# PCB__ARDUINO_APDS9960.net
KiCad netlist of a schematic drawn in EAGLE
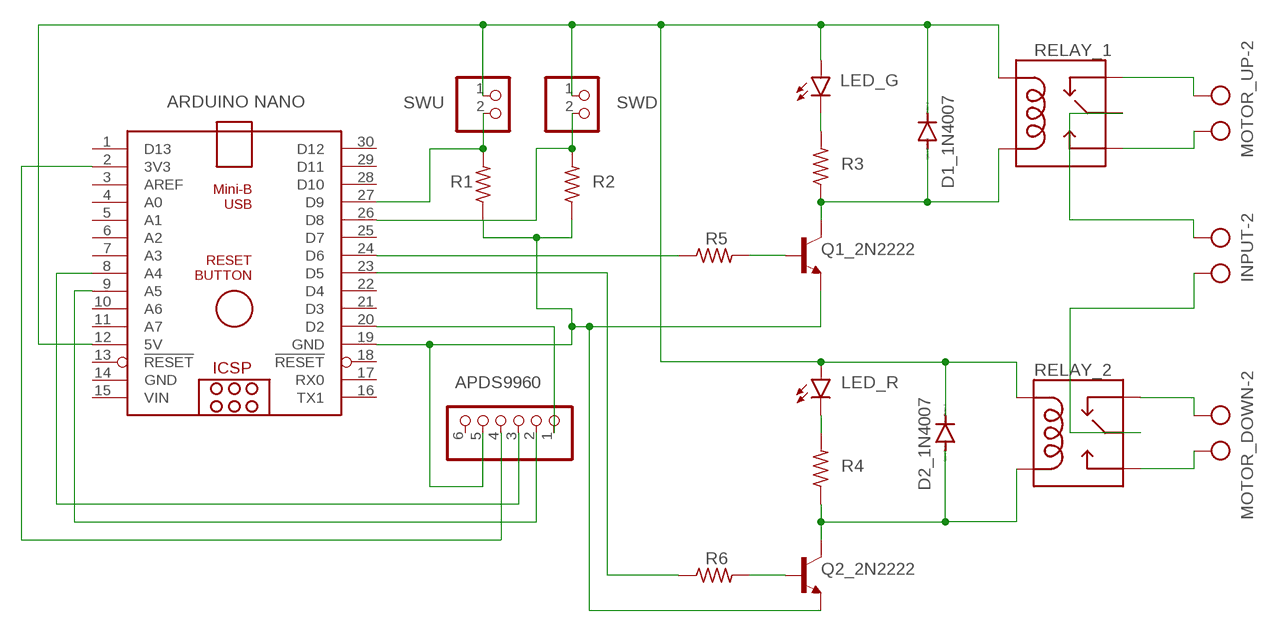
[diagram p0: schematic, sheet 1]

(export (version "E")
  (design (tool "Eeschema 10.0.6"))
  (components
    (comp (ref "APDS9960")
      (value "PINHD-1X6")
      (footprint "eagle-import:1X06")
      (libsource (lib "eagle-import") (part "PINHD-1X6"))
    )
    (comp (ref "ARDUINO_NANO")
      (value "ARDUINO NANO")
      (footprint "eagle-import:ARDUINO_NANO")
      (libsource (lib "eagle-import") (part "ARDUINO_NANO"))
    )
    (comp (ref "D1_1N4007")
      (value "1N4446")
      (footprint "eagle-import:DO35-10")
      (libsource (lib "eagle-import") (part "1N4446"))
    )
    (comp (ref "D2_1N4007")
      (value "1N4446")
      (footprint "eagle-import:DO35-10")
      (libsource (lib "eagle-import") (part "1N4446"))
    )
    (comp (ref "INPUT")
      (value "AK500/2")
      (footprint "eagle-import:AK500_2")
      (libsource (lib "eagle-import") (part "AK500/2"))
    )
    (comp (ref "LED_G")
      (value "TLLY4400")
      (footprint "eagle-import:LED3MM")
      (fields (field (name "MF") "VISHAY SEMICONDUCTOR"))
      (libsource (lib "eagle-import") (part "TLLY4400"))
    )
    (comp (ref "LED_R")
      (value "TLLY4400")
      (footprint "eagle-import:LED3MM")
      (fields (field (name "MF") "VISHAY SEMICONDUCTOR"))
      (libsource (lib "eagle-import") (part "TLLY4400"))
    )
    (comp (ref "MOTOR_DOWN")
      (value "AK500/2")
      (footprint "eagle-import:AK500_2")
      (libsource (lib "eagle-import") (part "AK500/2"))
    )
    (comp (ref "MOTOR_UP")
      (value "AK500/2")
      (footprint "eagle-import:AK500_2")
      (libsource (lib "eagle-import") (part "AK500/2"))
    )
    (comp (ref "Q1_2N2222")
      (value "2N3904")
      (footprint "eagle-import:TO92")
      (libsource (lib "eagle-import") (part "2N3904"))
    )
    (comp (ref "Q2_2N2222")
      (value "2N3904")
      (footprint "eagle-import:TO92")
      (libsource (lib "eagle-import") (part "2N3904"))
    )
    (comp (ref "R1")
      (value "R-US_0207/10")
      (footprint "eagle-import:0207_10")
      (libsource (lib "eagle-import") (part "R-US_0207/10"))
    )
    (comp (ref "R2")
      (value "R-US_0207/10")
      (footprint "eagle-import:0207_10")
      (libsource (lib "eagle-import") (part "R-US_0207/10"))
    )
    (comp (ref "R3")
      (value "R-US_0207/10")
      (footprint "eagle-import:0207_10")
      (libsource (lib "eagle-import") (part "R-US_0207/10"))
    )
    (comp (ref "R4")
      (value "R-US_0207/10")
      (footprint "eagle-import:0207_10")
      (libsource (lib "eagle-import") (part "R-US_0207/10"))
    )
    (comp (ref "R5")
      (value "R-US_0207/10")
      (footprint "eagle-import:0207_10")
      (libsource (lib "eagle-import") (part "R-US_0207/10"))
    )
    (comp (ref "R6")
      (value "R-US_0207/10")
      (footprint "eagle-import:0207_10")
      (libsource (lib "eagle-import") (part "R-US_0207/10"))
    )
    (comp (ref "RELAY_1")
      (value "RELAYPTH")
      (footprint "eagle-import:SRD-05VDC-SL-C")
      (libsource (lib "eagle-import") (part "RELAYPTH"))
    )
    (comp (ref "RELAY_2")
      (value "RELAYPTH")
      (footprint "eagle-import:SRD-05VDC-SL-C")
      (libsource (lib "eagle-import") (part "RELAYPTH"))
    )
    (comp (ref "SWD")
      (value "PINHD-1X2")
      (footprint "eagle-import:1X02")
      (libsource (lib "eagle-import") (part "PINHD-1X2"))
    )
    (comp (ref "SWU")
      (value "PINHD-1X2")
      (footprint "eagle-import:1X02")
      (libsource (lib "eagle-import") (part "PINHD-1X2"))
    )
  )
  (nets
    (net (code "1") (name "/GND") (class "Default")
      (node (ref "ARDUINO_NANO") (pin "14") (pinfunction "GND_14") (pintype "power_in"))
    )
    (net (code "2") (name "/VIN") (class "Default")
      (node (ref "ARDUINO_NANO") (pin "15") (pinfunction "VIN_15") (pintype "power_in"))
    )
    (net (code "3") (name "Net-(ARDUINO_NANO-3V3)") (class "Default")
      (node (ref "APDS9960") (pin "4") (pinfunction "4_4") (pintype "passive"))
      (node (ref "ARDUINO_NANO") (pin "2") (pinfunction "3V3_2") (pintype "output"))
    )
    (net (code "4") (name "Net-(ARDUINO_NANO-5V)") (class "Default")
      (node (ref "ARDUINO_NANO") (pin "12") (pinfunction "5V_12") (pintype "power_in"))
      (node (ref "D1_1N4007") (pin "C") (pinfunction "C_C") (pintype "passive"))
      (node (ref "D2_1N4007") (pin "C") (pinfunction "C_C") (pintype "passive"))
      (node (ref "LED_G") (pin "A") (pinfunction "A_A") (pintype "passive"))
      (node (ref "LED_R") (pin "A") (pinfunction "A_A") (pintype "passive"))
      (node (ref "RELAY_1") (pin "COIL1") (pinfunction "COIL1_COIL1") (pintype "bidirectional"))
      (node (ref "RELAY_2") (pin "COIL1") (pinfunction "COIL1_COIL1") (pintype "bidirectional"))
      (node (ref "SWD") (pin "1") (pinfunction "1_1") (pintype "passive"))
      (node (ref "SWU") (pin "1") (pinfunction "1_1") (pintype "passive"))
    )
    (net (code "5") (name "Net-(ARDUINO_NANO-A4)") (class "Default")
      (node (ref "APDS9960") (pin "3") (pinfunction "3_3") (pintype "passive"))
      (node (ref "ARDUINO_NANO") (pin "8") (pinfunction "A4_8") (pintype "bidirectional"))
    )
    (net (code "6") (name "Net-(ARDUINO_NANO-A5)") (class "Default")
      (node (ref "APDS9960") (pin "2") (pinfunction "2_2") (pintype "passive"))
      (node (ref "ARDUINO_NANO") (pin "9") (pinfunction "A5_9") (pintype "bidirectional"))
    )
    (net (code "7") (name "Net-(ARDUINO_NANO-D2)") (class "Default")
      (node (ref "APDS9960") (pin "1") (pinfunction "1_1") (pintype "passive"))
      (node (ref "ARDUINO_NANO") (pin "20") (pinfunction "D2_20") (pintype "bidirectional"))
    )
    (net (code "8") (name "Net-(ARDUINO_NANO-D5)") (class "Default")
      (node (ref "ARDUINO_NANO") (pin "23") (pinfunction "D5_23") (pintype "bidirectional"))
      (node (ref "R6") (pin "1") (pinfunction "1_1") (pintype "passive"))
    )
    (net (code "9") (name "Net-(ARDUINO_NANO-D6)") (class "Default")
      (node (ref "ARDUINO_NANO") (pin "24") (pinfunction "D6_24") (pintype "bidirectional"))
      (node (ref "R5") (pin "1") (pinfunction "1_1") (pintype "passive"))
    )
    (net (code "10") (name "Net-(ARDUINO_NANO-D8)") (class "Default")
      (node (ref "ARDUINO_NANO") (pin "26") (pinfunction "D8_26") (pintype "bidirectional"))
      (node (ref "R2") (pin "2") (pinfunction "2_2") (pintype "passive"))
      (node (ref "SWD") (pin "2") (pinfunction "2_2") (pintype "passive"))
    )
    (net (code "11") (name "Net-(ARDUINO_NANO-D9)") (class "Default")
      (node (ref "ARDUINO_NANO") (pin "27") (pinfunction "D9_27") (pintype "bidirectional"))
      (node (ref "R1") (pin "2") (pinfunction "2_2") (pintype "passive"))
      (node (ref "SWU") (pin "2") (pinfunction "2_2") (pintype "passive"))
    )
    (net (code "12") (name "Net-(INPUTA-KL)") (class "Default")
      (node (ref "INPUT") (pin "1") (pinfunction "KL_1") (pintype "passive"))
      (node (ref "RELAY_2") (pin "SWCOMMON") (pinfunction "SWCOMMON_SWCOMMON") (pintype "bidirectional"))
    )
    (net (code "13") (name "Net-(INPUTB-KL)") (class "Default")
      (node (ref "INPUT") (pin "2") (pinfunction "KL_2") (pintype "passive"))
      (node (ref "RELAY_1") (pin "SWCOMMON") (pinfunction "SWCOMMON_SWCOMMON") (pintype "bidirectional"))
    )
    (net (code "14") (name "Net-(LED_G-C)") (class "Default")
      (node (ref "LED_G") (pin "K") (pinfunction "C_K") (pintype "passive"))
      (node (ref "R3") (pin "2") (pinfunction "2_2") (pintype "passive"))
    )
    (net (code "15") (name "Net-(LED_R-C)") (class "Default")
      (node (ref "LED_R") (pin "K") (pinfunction "C_K") (pintype "passive"))
      (node (ref "R4") (pin "2") (pinfunction "2_2") (pintype "passive"))
    )
    (net (code "16") (name "Net-(MOTOR_DOWNA-KL)") (class "Default")
      (node (ref "MOTOR_DOWN") (pin "1") (pinfunction "KL_1") (pintype "passive"))
      (node (ref "RELAY_2") (pin "SWOPEN") (pinfunction "SWOPEN_SWOPEN") (pintype "bidirectional"))
    )
    (net (code "17") (name "Net-(MOTOR_DOWNB-KL)") (class "Default")
      (node (ref "MOTOR_DOWN") (pin "2") (pinfunction "KL_2") (pintype "passive"))
      (node (ref "RELAY_2") (pin "SWCLOSED") (pinfunction "SWCLOSE_SWCLOSED") (pintype "bidirectional"))
    )
    (net (code "18") (name "Net-(MOTOR_UPA-KL)") (class "Default")
      (node (ref "MOTOR_UP") (pin "1") (pinfunction "KL_1") (pintype "passive"))
      (node (ref "RELAY_1") (pin "SWOPEN") (pinfunction "SWOPEN_SWOPEN") (pintype "bidirectional"))
    )
    (net (code "19") (name "Net-(MOTOR_UPB-KL)") (class "Default")
      (node (ref "MOTOR_UP") (pin "2") (pinfunction "KL_2") (pintype "passive"))
      (node (ref "RELAY_1") (pin "SWCLOSED") (pinfunction "SWCLOSE_SWCLOSED") (pintype "bidirectional"))
    )
    (net (code "20") (name "Net-(Q1_2N2222-B)") (class "Default")
      (node (ref "Q1_2N2222") (pin "2") (pinfunction "B_2") (pintype "passive"))
      (node (ref "R5") (pin "2") (pinfunction "2_2") (pintype "passive"))
    )
    (net (code "21") (name "Net-(Q1_2N2222-C)") (class "Default")
      (node (ref "D1_1N4007") (pin "A") (pinfunction "A_A") (pintype "passive"))
      (node (ref "Q1_2N2222") (pin "1") (pinfunction "C_1") (pintype "passive"))
      (node (ref "R3") (pin "1") (pinfunction "1_1") (pintype "passive"))
      (node (ref "RELAY_1") (pin "COIL0") (pinfunction "COIL0_COIL0") (pintype "bidirectional"))
    )
    (net (code "22") (name "Net-(Q1_2N2222-E)") (class "Default")
      (node (ref "APDS9960") (pin "5") (pinfunction "5_5") (pintype "passive"))
      (node (ref "ARDUINO_NANO") (pin "19") (pinfunction "GND_19") (pintype "power_in"))
      (node (ref "Q1_2N2222") (pin "3") (pinfunction "E_3") (pintype "passive"))
      (node (ref "Q2_2N2222") (pin "3") (pinfunction "E_3") (pintype "passive"))
      (node (ref "R1") (pin "1") (pinfunction "1_1") (pintype "passive"))
      (node (ref "R2") (pin "1") (pinfunction "1_1") (pintype "passive"))
    )
    (net (code "23") (name "Net-(Q2_2N2222-B)") (class "Default")
      (node (ref "Q2_2N2222") (pin "2") (pinfunction "B_2") (pintype "passive"))
      (node (ref "R6") (pin "2") (pinfunction "2_2") (pintype "passive"))
    )
    (net (code "24") (name "Net-(Q2_2N2222-C)") (class "Default")
      (node (ref "D2_1N4007") (pin "A") (pinfunction "A_A") (pintype "passive"))
      (node (ref "Q2_2N2222") (pin "1") (pinfunction "C_1") (pintype "passive"))
      (node (ref "R4") (pin "1") (pinfunction "1_1") (pintype "passive"))
      (node (ref "RELAY_2") (pin "COIL0") (pinfunction "COIL0_COIL0") (pintype "bidirectional"))
    )
    (net (code "25") (name "unconnected-(APDS9960-Pad6)") (class "Default")
      (node (ref "APDS9960") (pin "6") (pinfunction "6_6") (pintype "passive"))
    )
    (net (code "26") (name "unconnected-(ARDUINO_NANO-A0-Pad4)") (class "Default")
      (node (ref "ARDUINO_NANO") (pin "4") (pinfunction "A0_4") (pintype "bidirectional"))
    )
    (net (code "27") (name "unconnected-(ARDUINO_NANO-A1-Pad5)") (class "Default")
      (node (ref "ARDUINO_NANO") (pin "5") (pinfunction "A1_5") (pintype "bidirectional"))
    )
    (net (code "28") (name "unconnected-(ARDUINO_NANO-A2-Pad6)") (class "Default")
      (node (ref "ARDUINO_NANO") (pin "6") (pinfunction "A2_6") (pintype "bidirectional"))
    )
    (net (code "29") (name "unconnected-(ARDUINO_NANO-A3-Pad7)") (class "Default")
      (node (ref "ARDUINO_NANO") (pin "7") (pinfunction "A3_7") (pintype "bidirectional"))
    )
    (net (code "30") (name "unconnected-(ARDUINO_NANO-A6-Pad10)") (class "Default")
      (node (ref "ARDUINO_NANO") (pin "10") (pinfunction "A6_10") (pintype "bidirectional"))
    )
    (net (code "31") (name "unconnected-(ARDUINO_NANO-A7-Pad11)") (class "Default")
      (node (ref "ARDUINO_NANO") (pin "11") (pinfunction "A7_11") (pintype "bidirectional"))
    )
    (net (code "32") (name "unconnected-(ARDUINO_NANO-AREF-Pad3)") (class "Default")
      (node (ref "ARDUINO_NANO") (pin "3") (pinfunction "AREF_3") (pintype "input"))
    )
    (net (code "33") (name "unconnected-(ARDUINO_NANO-D3-Pad21)") (class "Default")
      (node (ref "ARDUINO_NANO") (pin "21") (pinfunction "D3_21") (pintype "bidirectional"))
    )
    (net (code "34") (name "unconnected-(ARDUINO_NANO-D4-Pad22)") (class "Default")
      (node (ref "ARDUINO_NANO") (pin "22") (pinfunction "D4_22") (pintype "bidirectional"))
    )
    (net (code "35") (name "unconnected-(ARDUINO_NANO-D7-Pad25)") (class "Default")
      (node (ref "ARDUINO_NANO") (pin "25") (pinfunction "D7_25") (pintype "bidirectional"))
    )
    (net (code "36") (name "unconnected-(ARDUINO_NANO-D10-Pad28)") (class "Default")
      (node (ref "ARDUINO_NANO") (pin "28") (pinfunction "D10_28") (pintype "bidirectional"))
    )
    (net (code "37") (name "unconnected-(ARDUINO_NANO-D11-Pad29)") (class "Default")
      (node (ref "ARDUINO_NANO") (pin "29") (pinfunction "D11_29") (pintype "bidirectional"))
    )
    (net (code "38") (name "unconnected-(ARDUINO_NANO-D12-Pad30)") (class "Default")
      (node (ref "ARDUINO_NANO") (pin "30") (pinfunction "D12_30") (pintype "bidirectional"))
    )
    (net (code "39") (name "unconnected-(ARDUINO_NANO-D13-Pad1)") (class "Default")
      (node (ref "ARDUINO_NANO") (pin "1") (pinfunction "D13_1") (pintype "bidirectional"))
    )
    (net (code "40") (name "unconnected-(ARDUINO_NANO-RX0-Pad17)") (class "Default")
      (node (ref "ARDUINO_NANO") (pin "17") (pinfunction "RX0_17") (pintype "bidirectional"))
    )
    (net (code "41") (name "unconnected-(ARDUINO_NANO-TX1-Pad16)") (class "Default")
      (node (ref "ARDUINO_NANO") (pin "16") (pinfunction "TX1_16") (pintype "bidirectional"))
    )
    (net (code "42") (name "unconnected-(ARDUINO_NANO-~{RESET}-Pad13)") (class "Default")
      (node (ref "ARDUINO_NANO") (pin "13") (pinfunction "~{RESET}_13") (pintype "input"))
    )
    (net (code "43") (name "unconnected-(ARDUINO_NANO-~{RESET}-Pad18)") (class "Default")
      (node (ref "ARDUINO_NANO") (pin "18") (pinfunction "~{RESET}_18") (pintype "input"))
    )
  )
)
